# Sheet_V01.net
KiCad netlist of a schematic drawn in Altium Designer
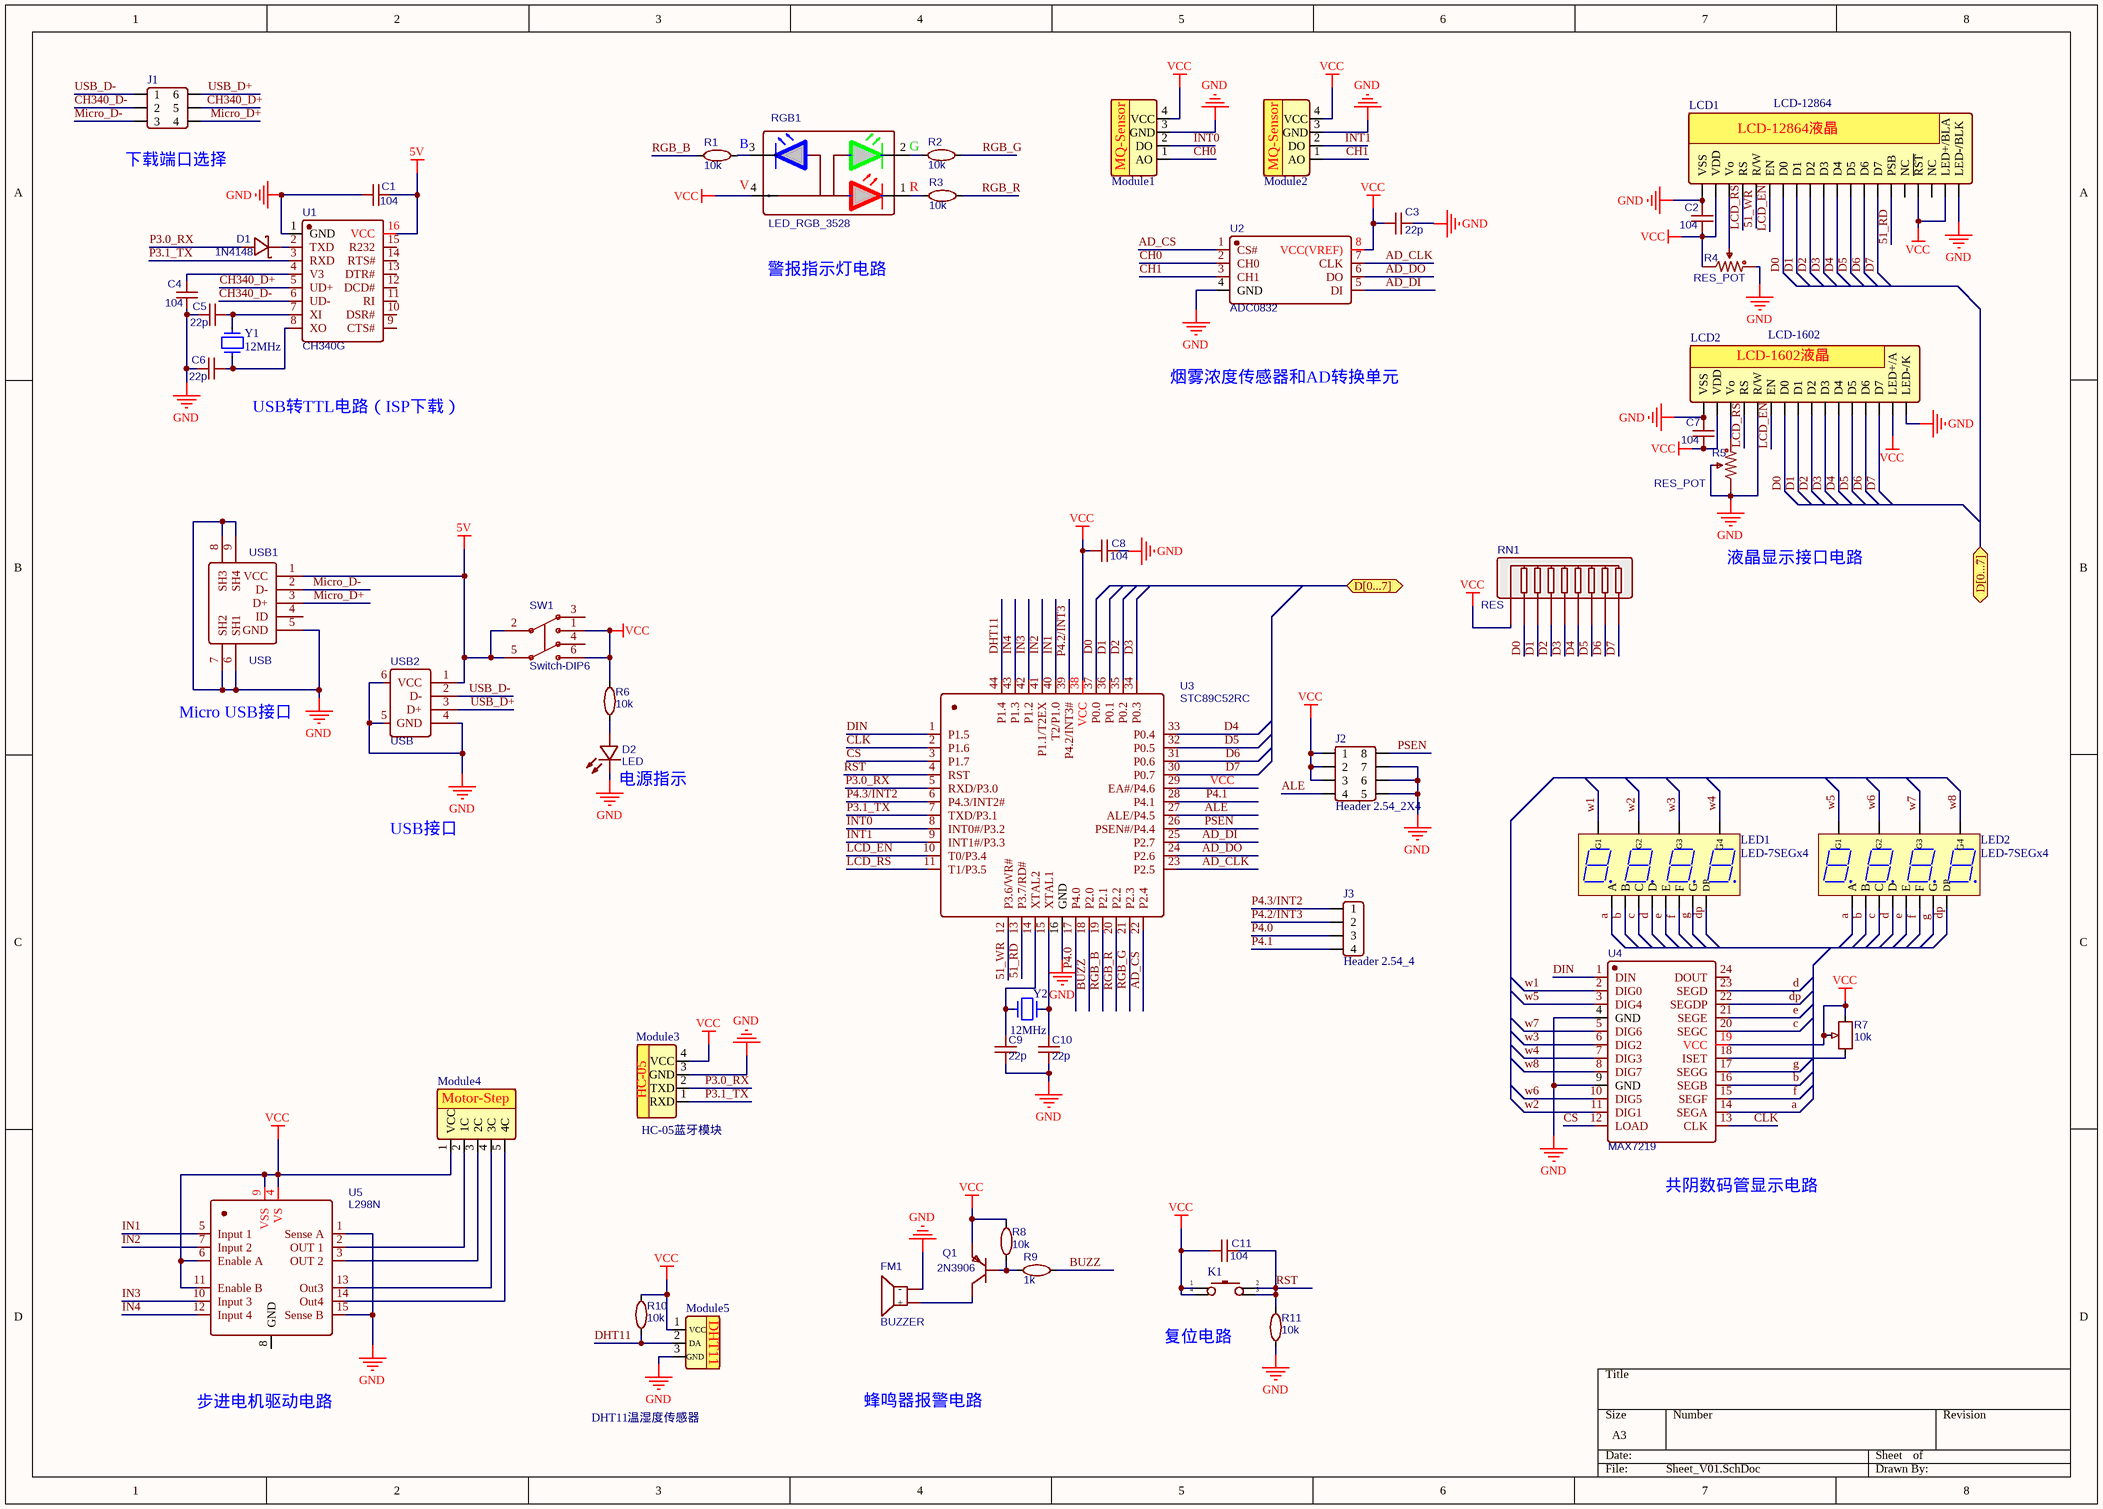
[diagram p0: Sheet_V01.SchDoc]

(export (version "E")
  (design (tool "Eeschema 10.0.6"))
  (components
    (comp (ref "C1")
      (value "104")
      (footprint "CAP_0805")
      (fields
        (field (name "BOM_SUPPLIER PART") "C307348")
        (field (name "BOM_MANUFACTURER PART") "CL10B104KB8WPNC")
        (field (name "CONTRIBUTOR") "LCSC")
      )
      (libsource (lib "LTC_Library1") (part "CAP_0805"))
    )
    (comp (ref "C2")
      (value "104")
      (footprint "CAP_0805")
      (fields
        (field (name "BOM_SUPPLIER PART") "C307348")
        (field (name "BOM_MANUFACTURER PART") "CL10B104KB8WPNC")
        (field (name "CONTRIBUTOR") "LCSC")
      )
      (libsource (lib "LTC_Library1") (part "CAP_0805"))
    )
    (comp (ref "C3")
      (value "22p")
      (footprint "CAP_0805")
      (fields
        (field (name "BOM_SUPPLIER PART") "C307348")
        (field (name "BOM_MANUFACTURER PART") "CL10B104KB8WPNC")
        (field (name "CONTRIBUTOR") "LCSC")
      )
      (libsource (lib "LTC_Library1") (part "CAP_0805"))
    )
    (comp (ref "C4")
      (value "104")
      (footprint "CAP_0805")
      (fields
        (field (name "BOM_SUPPLIER PART") "C307348")
        (field (name "BOM_MANUFACTURER PART") "CL10B104KB8WPNC")
        (field (name "CONTRIBUTOR") "LCSC")
      )
      (libsource (lib "LTC_Library1") (part "CAP_0805"))
    )
    (comp (ref "C5")
      (value "22p")
      (footprint "CAP_0805")
      (fields
        (field (name "BOM_SUPPLIER PART") "C307348")
        (field (name "BOM_MANUFACTURER PART") "CL10B104KB8WPNC")
        (field (name "CONTRIBUTOR") "LCSC")
      )
      (libsource (lib "LTC_Library1") (part "CAP_0805"))
    )
    (comp (ref "C6")
      (value "22p")
      (footprint "CAP_0805")
      (fields
        (field (name "BOM_SUPPLIER PART") "C307348")
        (field (name "BOM_MANUFACTURER PART") "CL10B104KB8WPNC")
        (field (name "CONTRIBUTOR") "LCSC")
      )
      (libsource (lib "LTC_Library1") (part "CAP_0805"))
    )
    (comp (ref "C7")
      (value "104")
      (footprint "CAP_0805")
      (fields
        (field (name "BOM_SUPPLIER PART") "C307348")
        (field (name "BOM_MANUFACTURER PART") "CL10B104KB8WPNC")
        (field (name "CONTRIBUTOR") "LCSC")
      )
      (libsource (lib "LTC_Library1") (part "CAP_0805"))
    )
    (comp (ref "C8")
      (value "104")
      (footprint "CAP_0805")
      (fields
        (field (name "BOM_SUPPLIER PART") "C307348")
        (field (name "BOM_MANUFACTURER PART") "CL10B104KB8WPNC")
        (field (name "CONTRIBUTOR") "LCSC")
      )
      (libsource (lib "LTC_Library1") (part "CAP_0805"))
    )
    (comp (ref "C9")
      (value "22p")
      (footprint "CAP_0805")
      (fields
        (field (name "BOM_SUPPLIER PART") "C307348")
        (field (name "BOM_MANUFACTURER PART") "CL10B104KB8WPNC")
        (field (name "CONTRIBUTOR") "LCSC")
      )
      (libsource (lib "LTC_Library1") (part "CAP_0805"))
    )
    (comp (ref "C10")
      (value "22p")
      (footprint "CAP_0805")
      (fields
        (field (name "BOM_SUPPLIER PART") "C307348")
        (field (name "BOM_MANUFACTURER PART") "CL10B104KB8WPNC")
        (field (name "CONTRIBUTOR") "LCSC")
      )
      (libsource (lib "LTC_Library1") (part "CAP_0805"))
    )
    (comp (ref "C11")
      (value "104")
      (footprint "CAP_0805")
      (fields
        (field (name "BOM_SUPPLIER PART") "C307348")
        (field (name "BOM_MANUFACTURER PART") "CL10B104KB8WPNC")
        (field (name "CONTRIBUTOR") "LCSC")
      )
      (libsource (lib "LTC_Library1") (part "CAP_0805"))
    )
    (comp (ref "D1")
      (value "1N4148")
      (footprint "SOD-123_1206")
      (fields
        (field (name "BOM_SUPPLIER PART") "C437199")
        (field (name "BOM_MANUFACTURER PART") "1N5819")
        (field (name "CONTRIBUTOR") "LCSC")
      )
      (libsource (lib "LTC_Library1") (part "1N4148"))
    )
    (comp (ref "D2")
      (value "LED")
      (footprint "LED_0805_R")
      (description "发光LED")
      (fields
        (field (name "BOM_MANUFACTURER PART") "D-G080508G1")
        (field (name "BOM_SUPPLIER PART") "C107402")
        (field (name "CONTRIBUTOR") "LCSC")
      )
      (libsource (lib "LTC_Library1") (part "LED_0805"))
    )
    (comp (ref "FM1")
      (value "BUZZER")
      (footprint "BUZZ-12*7.5")
      (description "蜂鸣器")
      (fields (field (name "BOM_MANUFACTURER PART") "TMB12A12") (field (name "BOM_SUPPLIER PART") "C96079"))
      (libsource (lib "LTC_Library1") (part "BUZZER"))
    )
    (comp (ref "J1")
      (value "Header 2.54_2X3")
      (footprint "Header 2.54_2X3")
      (libsource (lib "LTC_Library1") (part "Header 2.54_2X3"))
    )
    (comp (ref "J2")
      (value "Header 2.54_2X4")
      (footprint "Header 2.54_2X4")
      (libsource (lib "LTC_Library1") (part "Header 2.54_2X4"))
    )
    (comp (ref "J3")
      (value "Header 2.54_4")
      (footprint "Header 2.54X4")
      (libsource (lib "LTC_Library1") (part "Header 2.54_4"))
    )
    (comp (ref "K1")
      (value "DIP-Button_4P")
      (footprint "TSW DIP-6*6*6")
      (description "按键，直插，6*6*6")
      (libsource (lib "LTC_Library1") (part "DIP-Button_4P"))
    )
    (comp (ref "LCD1")
      (value "LCD-12864")
      (footprint "Header F 2.54X20")
      (libsource (lib "LTC_Library1") (part "LCD-12864液晶"))
    )
    (comp (ref "LCD2")
      (value "LCD-1602")
      (footprint "Header F 2.54X16")
      (libsource (lib "LTC_Library1") (part "LCD-1602液晶"))
    )
    (comp (ref "LED1")
      (value "LED-7SEGx4")
      (footprint "DISP_0.56_4")
      (libsource (lib "LTC_Library1") (part "LED-7SEGx4"))
    )
    (comp (ref "LED2")
      (value "LED-7SEGx4")
      (footprint "DISP_0.56_4")
      (libsource (lib "LTC_Library1") (part "LED-7SEGx4"))
    )
    (comp (ref "Module1")
      (value "MQ-2烟雾浓度传感器")
      (footprint "Header F 2.54X4")
      (libsource (lib "LTC_Library1") (part "MQ-2烟雾浓度传感器"))
    )
    (comp (ref "Module2")
      (value "MQ-2烟雾浓度传感器")
      (footprint "Header F 2.54X4")
      (libsource (lib "LTC_Library1") (part "MQ-2烟雾浓度传感器"))
    )
    (comp (ref "Module3")
      (value "HC-05蓝牙模块")
      (footprint "Header F 2.54X4")
      (libsource (lib "LTC_Library1") (part "HC-05蓝牙模块"))
    )
    (comp (ref "Module4")
      (value "5线4相步进电机")
      (footprint "XH_2.54_5P")
      (libsource (lib "LTC_Library1") (part "5线4相步进电机"))
    )
    (comp (ref "Module5")
      (value "DHT11温湿度传感器")
      (footprint "Header F 2.54X3")
      (libsource (lib "LTC_Library1") (part "DHT11温湿度传感器"))
    )
    (comp (ref "Q1")
      (value "2N3906")
      (footprint "TO_92A")
      (description "三极管PNP")
      (fields (field (name "BOM_SUPPLIER PART") "C305396") (field (name "CONTRIBUTOR") "LCSC"))
      (libsource (lib "LTC_Library1") (part "2N3906"))
    )
    (comp (ref "R1")
      (value "10k")
      (footprint "RES_0805")
      (fields
        (field (name "BOM_MANUFACTURER PART") "RC0402JR-07100KL")
        (field (name "BOM_SUPPLIER PART") "C106234")
      )
      (libsource (lib "LTC_Library1") (part "RES_0805"))
    )
    (comp (ref "R2")
      (value "10k")
      (footprint "RES_0805")
      (fields
        (field (name "BOM_MANUFACTURER PART") "RC0402JR-07100KL")
        (field (name "BOM_SUPPLIER PART") "C106234")
      )
      (libsource (lib "LTC_Library1") (part "RES_0805"))
    )
    (comp (ref "R3")
      (value "10k")
      (footprint "RES_0805")
      (fields
        (field (name "BOM_MANUFACTURER PART") "RC0402JR-07100KL")
        (field (name "BOM_SUPPLIER PART") "C106234")
      )
      (libsource (lib "LTC_Library1") (part "RES_0805"))
    )
    (comp (ref "R4")
      (value "RES_POT")
      (footprint "RES_POT-3362P")
      (description "可调电阻3362P")
      (fields
        (field (name "BOM_SUPPLIER PART") "C118947")
        (field (name "BOM_MANUFACTURER PART") "3362P-1-102")
        (field (name "CONTRIBUTOR") "LCSC")
      )
      (libsource (lib "") (part "RES_POT-3362P_1"))
    )
    (comp (ref "R5")
      (value "RES_POT")
      (footprint "RES_POT-3362P")
      (description "可调电阻3362P")
      (fields
        (field (name "BOM_SUPPLIER PART") "C118947")
        (field (name "BOM_MANUFACTURER PART") "3362P-1-102")
        (field (name "CONTRIBUTOR") "LCSC")
      )
      (libsource (lib "LTC_Library1") (part "RES_POT-3362P"))
    )
    (comp (ref "R6")
      (value "10k")
      (footprint "RES_0805")
      (fields
        (field (name "BOM_MANUFACTURER PART") "RC0402JR-07100KL")
        (field (name "BOM_SUPPLIER PART") "C106234")
      )
      (libsource (lib "LTC_Library1") (part "RES_0805"))
    )
    (comp (ref "R7")
      (value "10k")
      (footprint "RES_POT-3296W")
      (description "可调电阻3296W")
      (fields
        (field (name "BOM_SUPPLIER PART") "C118963")
        (field (name "BOM_MANUFACTURER PART") "3296W-1-104")
        (field (name "CONTRIBUTOR") "LCSC")
      )
      (libsource (lib "LTC_Library1") (part "RES_POT-3296W"))
    )
    (comp (ref "R8")
      (value "10k")
      (footprint "RES_0805")
      (fields
        (field (name "BOM_MANUFACTURER PART") "RC0402JR-07100KL")
        (field (name "BOM_SUPPLIER PART") "C106234")
      )
      (libsource (lib "LTC_Library1") (part "RES_0805"))
    )
    (comp (ref "R9")
      (value "1k")
      (footprint "RES_0805")
      (fields
        (field (name "BOM_MANUFACTURER PART") "RC0402JR-07100KL")
        (field (name "BOM_SUPPLIER PART") "C106234")
      )
      (libsource (lib "LTC_Library1") (part "RES_0805"))
    )
    (comp (ref "R10")
      (value "10k")
      (footprint "RES_0805")
      (fields
        (field (name "BOM_MANUFACTURER PART") "RC0402JR-07100KL")
        (field (name "BOM_SUPPLIER PART") "C106234")
      )
      (libsource (lib "LTC_Library1") (part "RES_0805"))
    )
    (comp (ref "R11")
      (value "10k")
      (footprint "RES_0805")
      (fields
        (field (name "BOM_MANUFACTURER PART") "RC0402JR-07100KL")
        (field (name "BOM_SUPPLIER PART") "C106234")
      )
      (libsource (lib "LTC_Library1") (part "RES_0805"))
    )
    (comp (ref "RGB1")
      (value "LED_RGB_3528")
      (footprint "LED_3528_RGB")
      (fields
        (field (name "BOM_MANUFACTURER PART") "FM-3528RGBA-HF")
        (field (name "BOM_SUPPLIER PART") "C108539")
        (field (name "CONTRIBUTOR") "LCSC")
      )
      (libsource (lib "LTC_Library1") (part "LED_RGB_3528"))
    )
    (comp (ref "RN1")
      (value "RES")
      (footprint "RES_8P")
      (description "直插排阻")
      (fields (field (name "BOM_MANUFACTURER PART") "A09-511J") (field (name "BOM_SUPPLIER PART") "C88134"))
      (libsource (lib "LTC_Library1") (part "RES-8-DIP"))
    )
    (comp (ref "SW1")
      (value "Switch-DIP6")
      (footprint "Switch_6")
      (description "6脚自锁开关")
      (fields (field (name "BOM_MANUFACTURER PART") "ESB33535") (field (name "BOM_SUPPLIER PART") "C79134"))
      (libsource (lib "LTC_Library1") (part "Switch-DIP6"))
    )
    (comp (ref "U1")
      (value "CH340G")
      (footprint "SOP-16")
      (fields (field (name "BOM_SUPPLIER PART") "C14267"))
      (libsource (lib "LTC_Library1") (part "CH340G"))
    )
    (comp (ref "U2")
      (value "ADC0832")
      (footprint "DIP_8")
      (fields
        (field (name "BOM_SUPPLIER PART") "C385862")
        (field (name "BOM_MANUFACTURER PART") "ADC0832CCN/NOPB")
        (field (name "CONTRIBUTOR") "LCSC")
      )
      (libsource (lib "LTC_Library1") (part "ADC0832"))
    )
    (comp (ref "U3")
      (value "STC89C52RC")
      (footprint "LQFP_44_10X10")
      (fields
        (field (name "BOM_MANUFACTURER PART") "STC89C52RC-40I")
        (field (name "BOM_SUPPLIER PART") "C8707")
      )
      (libsource (lib "LTC_Library1") (part "STC89C52RC_SMD"))
    )
    (comp (ref "U4")
      (value "MAX7219")
      (footprint "DIP_24")
      (fields (field (name "BOM_MANUFACTURER PART") "max7219cng") (field (name "BOM_SUPPLIER PART") "C29160"))
      (libsource (lib "LTC_Library1") (part "MAX7219"))
    )
    (comp (ref "U5")
      (value "L298N")
      (footprint "Multiwatt_15")
      (fields (field (name "BOM_SUPPLIER PART") "C434589") (field (name "CONTRIBUTOR") "LCSC"))
      (libsource (lib "LTC_Library1") (part "L298N"))
    )
    (comp (ref "USB1")
      (value "USB")
      (footprint "USB_Micro_DIP2")
      (fields
        (field (name "BOM_SUPPLIER PART") "C404969")
        (field (name "BOM_MANUFACTURER PART") "MicroXNJ")
        (field (name "CONTRIBUTOR") "LCSC")
      )
      (libsource (lib "LTC_Library1") (part "MicroUSB"))
    )
    (comp (ref "USB2")
      (value "USB")
      (footprint "USB-A-TH")
      (fields
        (field (name "BOM_SUPPLIER PART") "C404969")
        (field (name "BOM_MANUFACTURER PART") "MicroXNJ")
        (field (name "CONTRIBUTOR") "LCSC")
      )
      (libsource (lib "LTC_Library1") (part "USBA"))
    )
    (comp (ref "Y1")
      (value "12MHz")
      (footprint "XTAL1")
      (description "晶振")
      (libsource (lib "LTC_Library1") (part "XTAL-2"))
    )
    (comp (ref "Y2")
      (value "12MHz")
      (footprint "XTAL1")
      (description "晶振")
      (libsource (lib "LTC_Library1") (part "XTAL-2"))
    )
  )
  (nets
    (net (code "1") (name "/51_RD") (class "Default")
      (node (ref "LCD1") (pin "15") (pinfunction "PSB_15") (pintype "passive"))
      (node (ref "U3") (pin "13") (pinfunction "P3.7/RD#_13") (pintype "passive"))
    )
    (net (code "2") (name "/51_WR") (class "Default")
      (node (ref "LCD1") (pin "5") (pinfunction "R/W_5") (pintype "passive"))
      (node (ref "U3") (pin "12") (pinfunction "P3.6/WR#_12") (pintype "passive"))
    )
    (net (code "3") (name "/AD_CLK") (class "Default")
      (node (ref "U2") (pin "7") (pinfunction "CLK_7") (pintype "passive"))
      (node (ref "U3") (pin "23") (pinfunction "P2.5_23") (pintype "passive"))
    )
    (net (code "4") (name "/AD_CS") (class "Default")
      (node (ref "U2") (pin "1") (pinfunction "CS#_1") (pintype "passive"))
      (node (ref "U3") (pin "22") (pinfunction "P2.4_22") (pintype "passive"))
    )
    (net (code "5") (name "/AD_DI") (class "Default")
      (node (ref "U2") (pin "5") (pinfunction "DI_5") (pintype "passive"))
      (node (ref "U3") (pin "25") (pinfunction "P2.7_25") (pintype "passive"))
    )
    (net (code "6") (name "/AD_DO") (class "Default")
      (node (ref "U2") (pin "6") (pinfunction "DO_6") (pintype "passive"))
      (node (ref "U3") (pin "24") (pinfunction "P2.6_24") (pintype "passive"))
    )
    (net (code "7") (name "/ALE") (class "Default")
      (node (ref "J2") (pin "4") (pinfunction "4_4") (pintype "passive"))
      (node (ref "U3") (pin "27") (pinfunction "ALE/P4.5_27") (pintype "passive"))
    )
    (net (code "8") (name "/BUZZ") (class "Default")
      (node (ref "R9") (pin "1") (pinfunction "1_1") (pintype "passive"))
      (node (ref "U3") (pin "18") (pinfunction "P2.0_18") (pintype "passive"))
    )
    (net (code "9") (name "/CH0") (class "Default")
      (node (ref "Module1") (pin "1") (pinfunction "AO_1") (pintype "passive"))
      (node (ref "U2") (pin "2") (pinfunction "CH0_2") (pintype "passive"))
    )
    (net (code "10") (name "/CH1") (class "Default")
      (node (ref "Module2") (pin "1") (pinfunction "AO_1") (pintype "passive"))
      (node (ref "U2") (pin "3") (pinfunction "CH1_3") (pintype "passive"))
    )
    (net (code "11") (name "/CH340_D+") (class "Default")
      (node (ref "J1") (pin "5") (pinfunction "5_5") (pintype "passive"))
      (node (ref "U1") (pin "5") (pinfunction "UD+_5") (pintype "passive"))
    )
    (net (code "12") (name "/CH340_D-") (class "Default")
      (node (ref "J1") (pin "2") (pinfunction "2_2") (pintype "passive"))
      (node (ref "U1") (pin "6") (pinfunction "UD-_6") (pintype "passive"))
    )
    (net (code "13") (name "/CLK") (class "Default")
      (node (ref "U3") (pin "2") (pinfunction "P1.6_2") (pintype "passive"))
      (node (ref "U4") (pin "13") (pinfunction "CLK_13") (pintype "passive"))
    )
    (net (code "14") (name "/CS") (class "Default")
      (node (ref "U3") (pin "3") (pinfunction "P1.7_3") (pintype "passive"))
      (node (ref "U4") (pin "12") (pinfunction "LOAD_12") (pintype "passive"))
    )
    (net (code "15") (name "/D0") (class "Default")
      (node (ref "LCD1") (pin "7") (pinfunction "D0_7") (pintype "passive"))
      (node (ref "LCD2") (pin "7") (pinfunction "D0_7") (pintype "passive"))
      (node (ref "RN1") (pin "2") (pinfunction "2_2") (pintype "passive"))
      (node (ref "U3") (pin "37") (pinfunction "P0.0_37") (pintype "passive"))
    )
    (net (code "16") (name "/D1") (class "Default")
      (node (ref "LCD1") (pin "8") (pinfunction "D1_8") (pintype "passive"))
      (node (ref "LCD2") (pin "8") (pinfunction "D1_8") (pintype "passive"))
      (node (ref "RN1") (pin "3") (pinfunction "3_3") (pintype "passive"))
      (node (ref "U3") (pin "36") (pinfunction "P0.1_36") (pintype "passive"))
    )
    (net (code "17") (name "/D2") (class "Default")
      (node (ref "LCD1") (pin "9") (pinfunction "D2_9") (pintype "passive"))
      (node (ref "LCD2") (pin "9") (pinfunction "D2_9") (pintype "passive"))
      (node (ref "RN1") (pin "4") (pinfunction "4_4") (pintype "passive"))
      (node (ref "U3") (pin "35") (pinfunction "P0.2_35") (pintype "passive"))
    )
    (net (code "18") (name "/D3") (class "Default")
      (node (ref "LCD1") (pin "10") (pinfunction "D3_10") (pintype "passive"))
      (node (ref "LCD2") (pin "10") (pinfunction "D3_10") (pintype "passive"))
      (node (ref "RN1") (pin "5") (pinfunction "5_5") (pintype "passive"))
      (node (ref "U3") (pin "34") (pinfunction "P0.3_34") (pintype "passive"))
    )
    (net (code "19") (name "/D4") (class "Default")
      (node (ref "LCD1") (pin "11") (pinfunction "D4_11") (pintype "passive"))
      (node (ref "LCD2") (pin "11") (pinfunction "D4_11") (pintype "passive"))
      (node (ref "RN1") (pin "6") (pinfunction "6_6") (pintype "passive"))
      (node (ref "U3") (pin "33") (pinfunction "P0.4_33") (pintype "passive"))
    )
    (net (code "20") (name "/D5") (class "Default")
      (node (ref "LCD1") (pin "12") (pinfunction "D5_12") (pintype "passive"))
      (node (ref "LCD2") (pin "12") (pinfunction "D5_12") (pintype "passive"))
      (node (ref "RN1") (pin "7") (pinfunction "7_7") (pintype "passive"))
      (node (ref "U3") (pin "32") (pinfunction "P0.5_32") (pintype "passive"))
    )
    (net (code "21") (name "/D6") (class "Default")
      (node (ref "LCD1") (pin "13") (pinfunction "D6_13") (pintype "passive"))
      (node (ref "LCD2") (pin "13") (pinfunction "D6_13") (pintype "passive"))
      (node (ref "RN1") (pin "8") (pinfunction "8_8") (pintype "passive"))
      (node (ref "U3") (pin "31") (pinfunction "P0.6_31") (pintype "passive"))
    )
    (net (code "22") (name "/D7") (class "Default")
      (node (ref "LCD1") (pin "14") (pinfunction "D7_14") (pintype "passive"))
      (node (ref "LCD2") (pin "14") (pinfunction "D7_14") (pintype "passive"))
      (node (ref "RN1") (pin "9") (pinfunction "9_9") (pintype "passive"))
      (node (ref "U3") (pin "30") (pinfunction "P0.7_30") (pintype "passive"))
    )
    (net (code "23") (name "/DHT11") (class "Default")
      (node (ref "Module5") (pin "2") (pinfunction "DA_2") (pintype "passive"))
      (node (ref "R10") (pin "2") (pinfunction "2_2") (pintype "passive"))
      (node (ref "U3") (pin "44") (pinfunction "P1.4_44") (pintype "passive"))
    )
    (net (code "24") (name "/DIN") (class "Default")
      (node (ref "U3") (pin "1") (pinfunction "P1.5_1") (pintype "passive"))
      (node (ref "U4") (pin "1") (pinfunction "DIN_1") (pintype "passive"))
    )
    (net (code "26") (name "/IN1") (class "Default")
      (node (ref "U3") (pin "40") (pinfunction "T2/P1.0_40") (pintype "passive"))
      (node (ref "U5") (pin "5") (pinfunction "Input_1_5") (pintype "passive"))
    )
    (net (code "27") (name "/IN2") (class "Default")
      (node (ref "U3") (pin "41") (pinfunction "P1.1/T2EX_41") (pintype "passive"))
      (node (ref "U5") (pin "7") (pinfunction "Input_2_7") (pintype "passive"))
    )
    (net (code "28") (name "/IN3") (class "Default")
      (node (ref "U3") (pin "42") (pinfunction "P1.2_42") (pintype "passive"))
      (node (ref "U5") (pin "10") (pinfunction "Input_3_10") (pintype "passive"))
    )
    (net (code "29") (name "/IN4") (class "Default")
      (node (ref "U3") (pin "43") (pinfunction "P1.3_43") (pintype "passive"))
      (node (ref "U5") (pin "12") (pinfunction "Input_4_12") (pintype "passive"))
    )
    (net (code "30") (name "/INT0") (class "Default")
      (node (ref "Module1") (pin "2") (pinfunction "DO_2") (pintype "passive"))
      (node (ref "U3") (pin "8") (pinfunction "INT0#/P3.2_8") (pintype "passive"))
    )
    (net (code "31") (name "/INT1") (class "Default")
      (node (ref "Module2") (pin "2") (pinfunction "DO_2") (pintype "passive"))
      (node (ref "U3") (pin "9") (pinfunction "INT1#/P3.3_9") (pintype "passive"))
    )
    (net (code "32") (name "/LCD_EN") (class "Default")
      (node (ref "LCD1") (pin "6") (pinfunction "EN_6") (pintype "passive"))
      (node (ref "LCD2") (pin "6") (pinfunction "EN_6") (pintype "passive"))
      (node (ref "U3") (pin "10") (pinfunction "T0/P3.4_10") (pintype "passive"))
    )
    (net (code "33") (name "/LCD_RS") (class "Default")
      (node (ref "LCD1") (pin "4") (pinfunction "RS_4") (pintype "passive"))
      (node (ref "LCD2") (pin "4") (pinfunction "RS_4") (pintype "passive"))
      (node (ref "U3") (pin "11") (pinfunction "T1/P3.5_11") (pintype "passive"))
    )
    (net (code "34") (name "/Micro_D+") (class "Default")
      (node (ref "J1") (pin "4") (pinfunction "4_4") (pintype "passive"))
      (node (ref "USB1") (pin "3") (pinfunction "D+_3") (pintype "passive"))
    )
    (net (code "35") (name "/Micro_D-") (class "Default")
      (node (ref "J1") (pin "3") (pinfunction "3_3") (pintype "passive"))
      (node (ref "USB1") (pin "2") (pinfunction "D-_2") (pintype "passive"))
    )
    (net (code "36") (name "/P3.0_RX") (class "Default")
      (node (ref "D1") (pin "1") (pinfunction "A_1") (pintype "passive"))
      (node (ref "Module3") (pin "2") (pinfunction "TXD_2") (pintype "passive"))
      (node (ref "U3") (pin "5") (pinfunction "RXD/P3.0_5") (pintype "passive"))
    )
    (net (code "37") (name "/P3.1_TX") (class "Default")
      (node (ref "Module3") (pin "1") (pinfunction "RXD_1") (pintype "passive"))
      (node (ref "U1") (pin "3") (pinfunction "RXD_3") (pintype "passive"))
      (node (ref "U3") (pin "7") (pinfunction "TXD/P3.1_7") (pintype "passive"))
    )
    (net (code "38") (name "/P4.0") (class "Default")
      (node (ref "J3") (pin "3") (pinfunction "3_3") (pintype "passive"))
      (node (ref "U3") (pin "17") (pinfunction "P4.0_17") (pintype "passive"))
    )
    (net (code "39") (name "/P4.1") (class "Default")
      (node (ref "J3") (pin "4") (pinfunction "4_4") (pintype "passive"))
      (node (ref "U3") (pin "28") (pinfunction "P4.1_28") (pintype "passive"))
    )
    (net (code "40") (name "/P4.2{slash}INT3") (class "Default")
      (node (ref "J3") (pin "2") (pinfunction "2_2") (pintype "passive"))
      (node (ref "U3") (pin "39") (pinfunction "P4.2/INT3#_39") (pintype "passive"))
    )
    (net (code "41") (name "/P4.3{slash}INT2") (class "Default")
      (node (ref "J3") (pin "1") (pinfunction "1_1") (pintype "passive"))
      (node (ref "U3") (pin "6") (pinfunction "P4.3/INT2#_6") (pintype "passive"))
    )
    (net (code "42") (name "/PSEN") (class "Default")
      (node (ref "J2") (pin "8") (pinfunction "8_8") (pintype "passive"))
      (node (ref "U3") (pin "26") (pinfunction "PSEN#/P4.4_26") (pintype "passive"))
    )
    (net (code "43") (name "/RGB_B") (class "Default")
      (node (ref "R1") (pin "1") (pinfunction "1_1") (pintype "passive"))
      (node (ref "U3") (pin "19") (pinfunction "P2.1_19") (pintype "passive"))
    )
    (net (code "44") (name "/RGB_G") (class "Default")
      (node (ref "R2") (pin "2") (pinfunction "2_2") (pintype "passive"))
      (node (ref "U3") (pin "21") (pinfunction "P2.3_21") (pintype "passive"))
    )
    (net (code "45") (name "/RGB_R") (class "Default")
      (node (ref "R3") (pin "2") (pinfunction "2_2") (pintype "passive"))
      (node (ref "U3") (pin "20") (pinfunction "P2.2_20") (pintype "passive"))
    )
    (net (code "46") (name "/RST") (class "Default")
      (node (ref "C11") (pin "2") (pinfunction "2_2") (pintype "passive"))
      (node (ref "K1") (pin "2") (pintype "passive"))
      (node (ref "K1") (pin "3") (pintype "passive"))
      (node (ref "R11") (pin "1") (pinfunction "1_1") (pintype "passive"))
      (node (ref "U3") (pin "4") (pinfunction "RST_4") (pintype "passive"))
    )
    (net (code "47") (name "/USB_D+") (class "Default")
      (node (ref "J1") (pin "6") (pinfunction "6_6") (pintype "passive"))
      (node (ref "USB2") (pin "3") (pinfunction "D+_3") (pintype "passive"))
    )
    (net (code "48") (name "/USB_D-") (class "Default")
      (node (ref "J1") (pin "1") (pinfunction "1_1") (pintype "passive"))
      (node (ref "USB2") (pin "2") (pinfunction "D-_2") (pintype "passive"))
    )
    (net (code "49") (name "/a") (class "Default")
      (node (ref "LED1") (pin "11") (pinfunction "A_11") (pintype "passive"))
      (node (ref "LED2") (pin "11") (pinfunction "A_11") (pintype "passive"))
      (node (ref "U4") (pin "14") (pinfunction "SEGA_14") (pintype "passive"))
    )
    (net (code "50") (name "/b") (class "Default")
      (node (ref "LED1") (pin "7") (pinfunction "B_7") (pintype "passive"))
      (node (ref "LED2") (pin "7") (pinfunction "B_7") (pintype "passive"))
      (node (ref "U4") (pin "16") (pinfunction "SEGB_16") (pintype "passive"))
    )
    (net (code "51") (name "/c") (class "Default")
      (node (ref "LED1") (pin "4") (pinfunction "C_4") (pintype "passive"))
      (node (ref "LED2") (pin "4") (pinfunction "C_4") (pintype "passive"))
      (node (ref "U4") (pin "20") (pinfunction "SEGC_20") (pintype "passive"))
    )
    (net (code "52") (name "/d") (class "Default")
      (node (ref "LED1") (pin "2") (pinfunction "D_2") (pintype "passive"))
      (node (ref "LED2") (pin "2") (pinfunction "D_2") (pintype "passive"))
      (node (ref "U4") (pin "23") (pinfunction "SEGD_23") (pintype "passive"))
    )
    (net (code "53") (name "/dp") (class "Default")
      (node (ref "LED1") (pin "3") (pinfunction "DP_3") (pintype "passive"))
      (node (ref "LED2") (pin "3") (pinfunction "DP_3") (pintype "passive"))
      (node (ref "U4") (pin "22") (pinfunction "SEGDP_22") (pintype "passive"))
    )
    (net (code "54") (name "/e") (class "Default")
      (node (ref "LED1") (pin "1") (pinfunction "E_1") (pintype "passive"))
      (node (ref "LED2") (pin "1") (pinfunction "E_1") (pintype "passive"))
      (node (ref "U4") (pin "21") (pinfunction "SEGE_21") (pintype "passive"))
    )
    (net (code "55") (name "/f") (class "Default")
      (node (ref "LED1") (pin "10") (pinfunction "F_10") (pintype "passive"))
      (node (ref "LED2") (pin "10") (pinfunction "F_10") (pintype "passive"))
      (node (ref "U4") (pin "15") (pinfunction "SEGF_15") (pintype "passive"))
    )
    (net (code "56") (name "/g") (class "Default")
      (node (ref "LED1") (pin "5") (pinfunction "G_5") (pintype "passive"))
      (node (ref "LED2") (pin "5") (pinfunction "G_5") (pintype "passive"))
      (node (ref "U4") (pin "17") (pinfunction "SEGG_17") (pintype "passive"))
    )
    (net (code "57") (name "/w1") (class "Default")
      (node (ref "LED1") (pin "12") (pinfunction "G1_12") (pintype "passive"))
      (node (ref "U4") (pin "2") (pinfunction "DIG0_2") (pintype "passive"))
    )
    (net (code "58") (name "/w2") (class "Default")
      (node (ref "LED1") (pin "9") (pinfunction "G2_9") (pintype "passive"))
      (node (ref "U4") (pin "11") (pinfunction "DIG1_11") (pintype "passive"))
    )
    (net (code "59") (name "/w3") (class "Default")
      (node (ref "LED1") (pin "8") (pinfunction "G3_8") (pintype "passive"))
      (node (ref "U4") (pin "6") (pinfunction "DIG2_6") (pintype "passive"))
    )
    (net (code "60") (name "/w4") (class "Default")
      (node (ref "LED1") (pin "6") (pinfunction "G4_6") (pintype "passive"))
      (node (ref "U4") (pin "7") (pinfunction "DIG3_7") (pintype "passive"))
    )
    (net (code "61") (name "/w5") (class "Default")
      (node (ref "LED2") (pin "12") (pinfunction "G1_12") (pintype "passive"))
      (node (ref "U4") (pin "3") (pinfunction "DIG4_3") (pintype "passive"))
    )
    (net (code "62") (name "/w6") (class "Default")
      (node (ref "LED2") (pin "9") (pinfunction "G2_9") (pintype "passive"))
      (node (ref "U4") (pin "10") (pinfunction "DIG5_10") (pintype "passive"))
    )
    (net (code "63") (name "/w7") (class "Default")
      (node (ref "LED2") (pin "8") (pinfunction "G3_8") (pintype "passive"))
      (node (ref "U4") (pin "5") (pinfunction "DIG6_5") (pintype "passive"))
    )
    (net (code "64") (name "/w8") (class "Default")
      (node (ref "LED2") (pin "6") (pinfunction "G4_6") (pintype "passive"))
      (node (ref "U4") (pin "8") (pinfunction "DIG7_8") (pintype "passive"))
    )
    (net (code "65") (name "5V") (class "Default")
      (node (ref "C1") (pin "2") (pinfunction "2_2") (pintype "passive"))
      (node (ref "SW1") (pin "2") (pinfunction "C_2") (pintype "passive"))
      (node (ref "SW1") (pin "5") (pinfunction "C_5") (pintype "passive"))
      (node (ref "U1") (pin "16") (pinfunction "VCC_16") (pintype "passive"))
      (node (ref "USB1") (pin "1") (pinfunction "VCC_1") (pintype "passive"))
      (node (ref "USB2") (pin "1") (pinfunction "VCC_1") (pintype "passive"))
    )
    (net (code "66") (name "GND") (class "Default")
      (node (ref "C1") (pin "1") (pinfunction "1_1") (pintype "passive"))
      (node (ref "C10") (pin "2") (pinfunction "2_2") (pintype "passive"))
      (node (ref "C2") (pin "2") (pinfunction "2_2") (pintype "passive"))
      (node (ref "C3") (pin "2") (pinfunction "2_2") (pintype "passive"))
      (node (ref "C4") (pin "1") (pinfunction "1_1") (pintype "passive"))
      (node (ref "C5") (pin "1") (pinfunction "1_1") (pintype "passive"))
      (node (ref "C6") (pin "1") (pinfunction "1_1") (pintype "passive"))
      (node (ref "C7") (pin "2") (pinfunction "2_2") (pintype "passive"))
      (node (ref "C8") (pin "2") (pinfunction "2_2") (pintype "passive"))
      (node (ref "C9") (pin "2") (pinfunction "2_2") (pintype "passive"))
      (node (ref "D2") (pin "C") (pinfunction "C_C") (pintype "passive"))
      (node (ref "FM1") (pin "2") (pinfunction "－_2") (pintype "passive"))
      (node (ref "J2") (pin "5") (pinfunction "5_5") (pintype "passive"))
      (node (ref "J2") (pin "6") (pinfunction "6_6") (pintype "passive"))
      (node (ref "J2") (pin "7") (pinfunction "7_7") (pintype "passive"))
      (node (ref "LCD1") (pin "1") (pinfunction "VSS_1") (pintype "passive"))
      (node (ref "LCD1") (pin "20") (pinfunction "LED-/BLK_20") (pintype "passive"))
      (node (ref "LCD2") (pin "1") (pinfunction "VSS_1") (pintype "passive"))
      (node (ref "LCD2") (pin "16") (pinfunction "LED-/K_16") (pintype "passive"))
      (node (ref "LCD2") (pin "5") (pinfunction "R/W_5") (pintype "passive"))
      (node (ref "Module1") (pin "3") (pinfunction "GND_3") (pintype "passive"))
      (node (ref "Module2") (pin "3") (pinfunction "GND_3") (pintype "passive"))
      (node (ref "Module3") (pin "3") (pinfunction "GND_3") (pintype "passive"))
      (node (ref "Module5") (pin "3") (pinfunction "GND_3") (pintype "passive"))
      (node (ref "R11") (pin "2") (pinfunction "2_2") (pintype "passive"))
      (node (ref "R4") (pin "3") (pinfunction "3_3") (pintype "passive"))
      (node (ref "R5") (pin "1") (pinfunction "1_1") (pintype "passive"))
      (node (ref "R5") (pin "2") (pinfunction "2_2") (pintype "passive"))
      (node (ref "U1") (pin "1") (pinfunction "GND_1") (pintype "passive"))
      (node (ref "U2") (pin "4") (pinfunction "GND_4") (pintype "passive"))
      (node (ref "U3") (pin "16") (pinfunction "GND_16") (pintype "passive"))
      (node (ref "U4") (pin "4") (pinfunction "GND_4") (pintype "passive"))
      (node (ref "U4") (pin "9") (pinfunction "GND_9") (pintype "passive"))
      (node (ref "U5") (pin "1") (pinfunction "Sense_A_1") (pintype "passive"))
      (node (ref "U5") (pin "15") (pinfunction "Sense_B_15") (pintype "passive"))
      (node (ref "USB1") (pin "5") (pinfunction "GND_5") (pintype "passive"))
      (node (ref "USB1") (pin "6") (pinfunction "SH1_6") (pintype "passive"))
      (node (ref "USB1") (pin "7") (pinfunction "SH2_7") (pintype "passive"))
      (node (ref "USB1") (pin "8") (pinfunction "SH3_8") (pintype "passive"))
      (node (ref "USB1") (pin "9") (pinfunction "SH4_9") (pintype "passive"))
      (node (ref "USB2") (pin "4") (pinfunction "GND_4") (pintype "passive"))
      (node (ref "USB2") (pin "5") (pinfunction "SH4_5") (pintype "passive"))
      (node (ref "USB2") (pin "6") (pinfunction "SH1_6") (pintype "passive"))
    )
    (net (code "67") (name "Net-(D1-C)") (class "Default")
      (node (ref "D1") (pin "2") (pinfunction "C_2") (pintype "passive"))
      (node (ref "U1") (pin "2") (pinfunction "TXD_2") (pintype "passive"))
    )
    (net (code "68") (name "Net-(D2-PadA)") (class "Default")
      (node (ref "D2") (pin "A") (pinfunction "A_A") (pintype "passive"))
      (node (ref "R6") (pin "2") (pinfunction "2_2") (pintype "passive"))
    )
    (net (code "69") (name "Net-(FM1-+)") (class "Default")
      (node (ref "FM1") (pin "1") (pinfunction "+_1") (pintype "passive"))
      (node (ref "Q1") (pin "3") (pinfunction "C_3") (pintype "passive"))
    )
    (net (code "70") (name "Net-(LCD1-Vo)") (class "Default")
      (node (ref "LCD1") (pin "3") (pinfunction "Vo_3") (pintype "passive"))
      (node (ref "R4") (pin "2") (pinfunction "2_2") (pintype "passive"))
    )
    (net (code "71") (name "Net-(LCD2-Vo)") (class "Default")
      (node (ref "LCD2") (pin "3") (pinfunction "Vo_3") (pintype "passive"))
      (node (ref "R5") (pin "3") (pinfunction "3_3") (pintype "passive"))
    )
    (net (code "72") (name "Net-(Module4-1C)") (class "Default")
      (node (ref "Module4") (pin "2") (pinfunction "1C_2") (pintype "passive"))
      (node (ref "U5") (pin "2") (pinfunction "OUT_1_2") (pintype "passive"))
    )
    (net (code "73") (name "Net-(Module4-2C)") (class "Default")
      (node (ref "Module4") (pin "3") (pinfunction "2C_3") (pintype "passive"))
      (node (ref "U5") (pin "3") (pinfunction "OUT_2_3") (pintype "passive"))
    )
    (net (code "74") (name "Net-(Module4-3C)") (class "Default")
      (node (ref "Module4") (pin "4") (pinfunction "3C_4") (pintype "passive"))
      (node (ref "U5") (pin "13") (pinfunction "Out3_13") (pintype "passive"))
    )
    (net (code "75") (name "Net-(Module4-4C)") (class "Default")
      (node (ref "Module4") (pin "5") (pinfunction "4C_5") (pintype "passive"))
      (node (ref "U5") (pin "14") (pinfunction "Out4_14") (pintype "passive"))
    )
    (net (code "76") (name "Net-(Q1-B)") (class "Default")
      (node (ref "Q1") (pin "2") (pinfunction "B_2") (pintype "passive"))
      (node (ref "R8") (pin "2") (pinfunction "2_2") (pintype "passive"))
      (node (ref "R9") (pin "2") (pinfunction "2_2") (pintype "passive"))
    )
    (net (code "77") (name "Net-(R1-Pad2)") (class "Default")
      (node (ref "R1") (pin "2") (pinfunction "2_2") (pintype "passive"))
      (node (ref "RGB1") (pin "3") (pintype "passive"))
    )
    (net (code "78") (name "Net-(R2-Pad1)") (class "Default")
      (node (ref "R2") (pin "1") (pinfunction "1_1") (pintype "passive"))
      (node (ref "RGB1") (pin "2") (pintype "passive"))
    )
    (net (code "79") (name "Net-(R3-Pad1)") (class "Default")
      (node (ref "R3") (pin "1") (pinfunction "1_1") (pintype "passive"))
      (node (ref "RGB1") (pin "1") (pintype "passive"))
    )
    (net (code "80") (name "Net-(U1-V3)") (class "Default")
      (node (ref "C4") (pin "2") (pinfunction "2_2") (pintype "passive"))
      (node (ref "U1") (pin "4") (pinfunction "V3_4") (pintype "passive"))
    )
    (net (code "81") (name "Net-(U1-XI)") (class "Default")
      (node (ref "C5") (pin "2") (pinfunction "2_2") (pintype "passive"))
      (node (ref "U1") (pin "7") (pinfunction "XI_7") (pintype "passive"))
      (node (ref "Y1") (pin "2") (pinfunction "2_2") (pintype "passive"))
    )
    (net (code "82") (name "Net-(U1-XO)") (class "Default")
      (node (ref "C6") (pin "2") (pinfunction "2_2") (pintype "passive"))
      (node (ref "U1") (pin "8") (pinfunction "XO_8") (pintype "passive"))
      (node (ref "Y1") (pin "1") (pinfunction "1_1") (pintype "passive"))
    )
    (net (code "83") (name "Net-(U3-XTAL1)") (class "Default")
      (node (ref "C10") (pin "1") (pinfunction "1_1") (pintype "passive"))
      (node (ref "U3") (pin "15") (pinfunction "XTAL1_15") (pintype "passive"))
      (node (ref "Y2") (pin "2") (pinfunction "2_2") (pintype "passive"))
    )
    (net (code "84") (name "Net-(U3-XTAL2)") (class "Default")
      (node (ref "C9") (pin "1") (pinfunction "1_1") (pintype "passive"))
      (node (ref "U3") (pin "14") (pinfunction "XTAL2_14") (pintype "passive"))
      (node (ref "Y2") (pin "1") (pinfunction "1_1") (pintype "passive"))
    )
    (net (code "85") (name "Net-(U4-ISET)") (class "Default")
      (node (ref "R7") (pin "1") (pinfunction "1_1") (pintype "passive"))
      (node (ref "U4") (pin "18") (pinfunction "ISET_18") (pintype "passive"))
    )
    (net (code "86") (name "VCC") (class "Default")
      (node (ref "C11") (pin "1") (pinfunction "1_1") (pintype "passive"))
      (node (ref "C2") (pin "1") (pinfunction "1_1") (pintype "passive"))
      (node (ref "C3") (pin "1") (pinfunction "1_1") (pintype "passive"))
      (node (ref "C7") (pin "1") (pinfunction "1_1") (pintype "passive"))
      (node (ref "C8") (pin "1") (pinfunction "1_1") (pintype "passive"))
      (node (ref "J2") (pin "1") (pinfunction "1_1") (pintype "passive"))
      (node (ref "J2") (pin "2") (pinfunction "2_2") (pintype "passive"))
      (node (ref "J2") (pin "3") (pinfunction "3_3") (pintype "passive"))
      (node (ref "K1") (pin "1") (pintype "passive"))
      (node (ref "K1") (pin "4") (pintype "passive"))
      (node (ref "LCD1") (pin "17") (pinfunction "~{RST}_17") (pintype "passive"))
      (node (ref "LCD1") (pin "19") (pinfunction "LED+/BLA_19") (pintype "passive"))
      (node (ref "LCD1") (pin "2") (pinfunction "VDD_2") (pintype "passive"))
      (node (ref "LCD2") (pin "15") (pinfunction "LED+/A_15") (pintype "passive"))
      (node (ref "LCD2") (pin "2") (pinfunction "VDD_2") (pintype "passive"))
      (node (ref "Module1") (pin "4") (pinfunction "VCC_4") (pintype "passive"))
      (node (ref "Module2") (pin "4") (pinfunction "VCC_4") (pintype "passive"))
      (node (ref "Module3") (pin "4") (pinfunction "VCC_4") (pintype "passive"))
      (node (ref "Module4") (pin "1") (pinfunction "VCC_1") (pintype "passive"))
      (node (ref "Module5") (pin "1") (pinfunction "VCC_1") (pintype "passive"))
      (node (ref "Q1") (pin "1") (pinfunction "E_1") (pintype "passive"))
      (node (ref "R10") (pin "1") (pinfunction "1_1") (pintype "passive"))
      (node (ref "R4") (pin "1") (pinfunction "1_1") (pintype "passive"))
      (node (ref "R6") (pin "1") (pinfunction "1_1") (pintype "passive"))
      (node (ref "R7") (pin "2") (pinfunction "2_2") (pintype "passive"))
      (node (ref "R7") (pin "3") (pinfunction "3_3") (pintype "passive"))
      (node (ref "R8") (pin "1") (pinfunction "1_1") (pintype "passive"))
      (node (ref "RGB1") (pin "4") (pintype "passive"))
      (node (ref "RN1") (pin "1") (pinfunction "1_1") (pintype "passive"))
      (node (ref "SW1") (pin "1") (pinfunction "ON_1") (pintype "passive"))
      (node (ref "SW1") (pin "6") (pinfunction "ON_6") (pintype "passive"))
      (node (ref "U2") (pin "8") (pinfunction "VCC(VREF)_8") (pintype "passive"))
      (node (ref "U3") (pin "29") (pinfunction "EA#/P4.6_29") (pintype "passive"))
      (node (ref "U3") (pin "38") (pinfunction "VCC_38") (pintype "passive"))
      (node (ref "U4") (pin "19") (pinfunction "VCC_19") (pintype "passive"))
      (node (ref "U5") (pin "11") (pinfunction "Enable_B_11") (pintype "passive"))
      (node (ref "U5") (pin "4") (pinfunction "VS_4") (pintype "passive"))
      (node (ref "U5") (pin "6") (pinfunction "Enable_A_6") (pintype "passive"))
      (node (ref "U5") (pin "9") (pinfunction "VSS_9") (pintype "passive"))
    )
    (net (code "87") (name "unconnected-(LCD1-NC-Pad16)") (class "Default")
      (node (ref "LCD1") (pin "16") (pinfunction "NC_16") (pintype "passive"))
    )
    (net (code "88") (name "unconnected-(LCD1-NC-Pad18)") (class "Default")
      (node (ref "LCD1") (pin "18") (pinfunction "NC_18") (pintype "passive"))
    )
    (net (code "89") (name "unconnected-(SW1-NC-Pad3)") (class "Default")
      (node (ref "SW1") (pin "3") (pinfunction "NC_3") (pintype "passive"))
    )
    (net (code "90") (name "unconnected-(SW1-NC-Pad4)") (class "Default")
      (node (ref "SW1") (pin "4") (pinfunction "NC_4") (pintype "passive"))
    )
    (net (code "91") (name "unconnected-(U1-CTS#-Pad9)") (class "Default")
      (node (ref "U1") (pin "9") (pinfunction "CTS#_9") (pintype "passive"))
    )
    (net (code "92") (name "unconnected-(U1-DCD#-Pad12)") (class "Default")
      (node (ref "U1") (pin "12") (pinfunction "DCD#_12") (pintype "passive"))
    )
    (net (code "93") (name "unconnected-(U1-DSR#-Pad10)") (class "Default")
      (node (ref "U1") (pin "10") (pinfunction "DSR#_10") (pintype "passive"))
    )
    (net (code "94") (name "unconnected-(U1-DTR#-Pad13)") (class "Default")
      (node (ref "U1") (pin "13") (pinfunction "DTR#_13") (pintype "passive"))
    )
    (net (code "95") (name "unconnected-(U1-R232-Pad15)") (class "Default")
      (node (ref "U1") (pin "15") (pinfunction "R232_15") (pintype "passive"))
    )
    (net (code "96") (name "unconnected-(U1-RI-Pad11)") (class "Default")
      (node (ref "U1") (pin "11") (pinfunction "RI_11") (pintype "passive"))
    )
    (net (code "97") (name "unconnected-(U1-RTS#-Pad14)") (class "Default")
      (node (ref "U1") (pin "14") (pinfunction "RTS#_14") (pintype "passive"))
    )
    (net (code "98") (name "unconnected-(U4-DOUT-Pad24)") (class "Default")
      (node (ref "U4") (pin "24") (pinfunction "DOUT_24") (pintype "passive"))
    )
    (net (code "99") (name "unconnected-(U5-GND-Pad8)") (class "Default")
      (node (ref "U5") (pin "8") (pinfunction "GND_8") (pintype "passive"))
    )
    (net (code "100") (name "unconnected-(USB1-ID-Pad4)") (class "Default")
      (node (ref "USB1") (pin "4") (pinfunction "ID_4") (pintype "passive"))
    )
  )
)
